# datalogger.net
KiCad netlist of a schematic drawn in Altium Designer
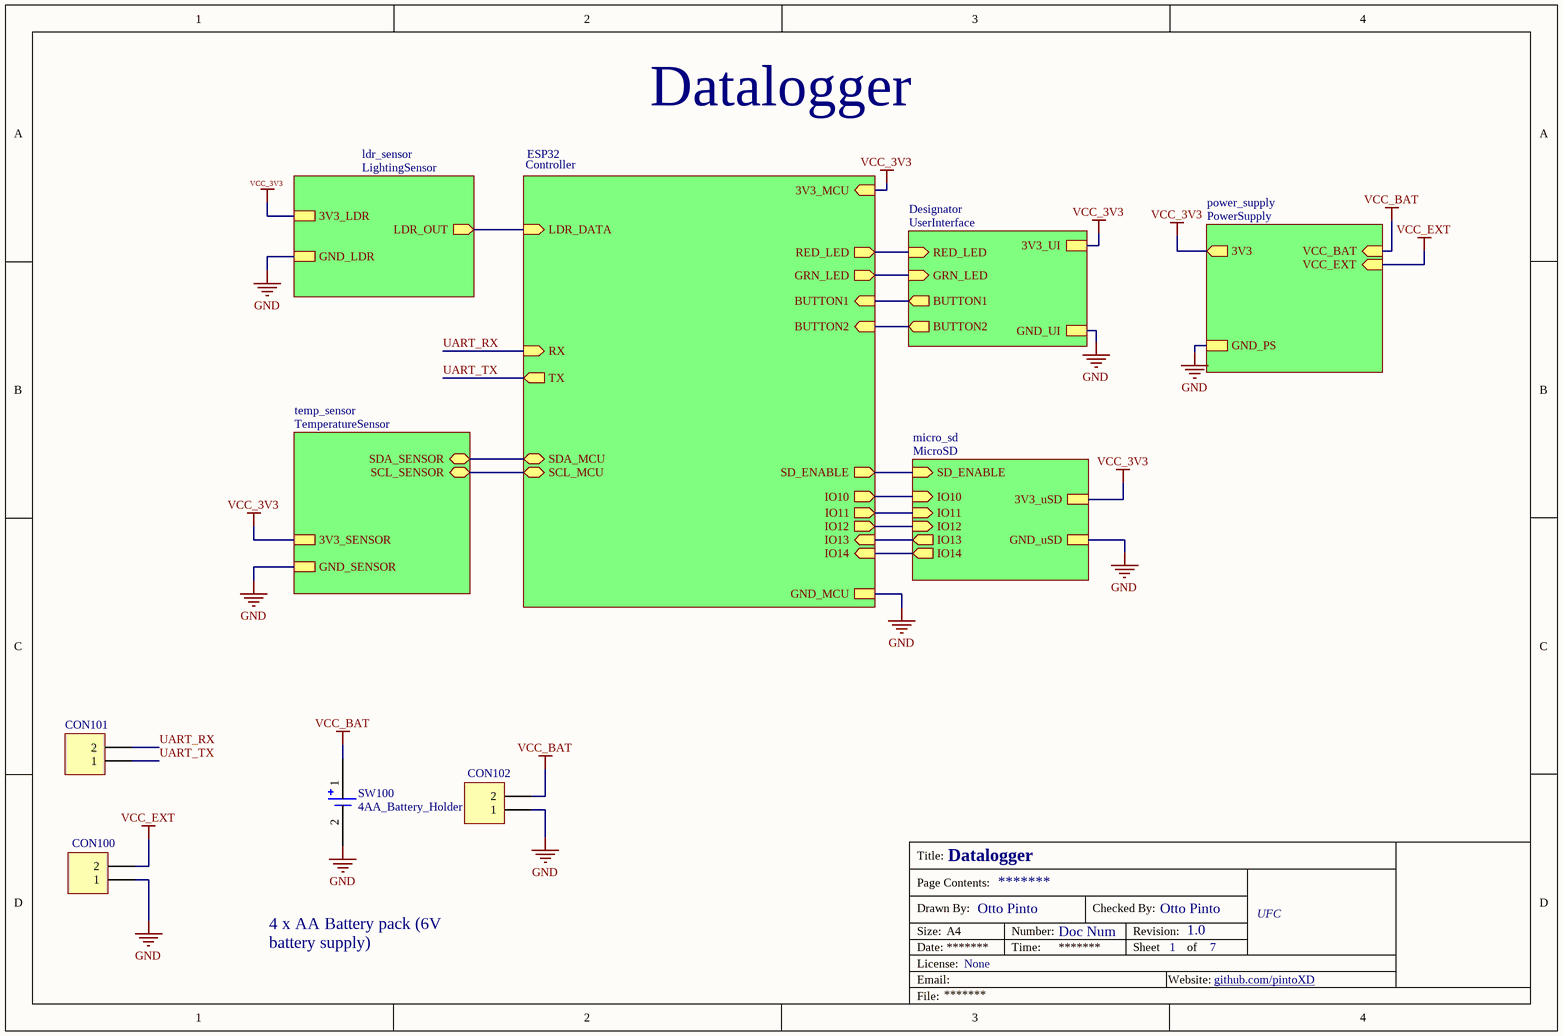
[diagram p0: datalogger.SchDoc]

(export (version "E")
  (design (tool "Eeschema 10.0.6"))
  (components
    (comp (ref "CON100")
      (value "PIN HEADER 2POS")
      (footprint "FP-TSW-102-07-G-S-MFG")
      (description "Conn Unshrouded Header HDR 2 POS 2.54mm Solder ST Top Entry Thru-Hole Bulk")
      (fields (field (name "MANUFACTURER PART NUMBER") "TSW-102-07-G-S"))
      (libsource (lib "Mobit Brasil Ltda") (part "Pin Header 2POS"))
    )
    (comp (ref "CON101")
      (value "PIN HEADER 2POS")
      (footprint "FP-TSW-102-07-G-S-MFG")
      (description "Conn Unshrouded Header HDR 2 POS 2.54mm Solder ST Top Entry Thru-Hole Bulk")
      (fields (field (name "MANUFACTURER PART NUMBER") "TSW-102-07-G-S"))
      (libsource (lib "Mobit Brasil Ltda") (part "Pin Header 2POS"))
    )
    (comp (ref "CON102")
      (value "PIN HEADER 2POS")
      (footprint "FP-TSW-102-07-G-S-MFG")
      (description "Conn Unshrouded Header HDR 2 POS 2.54mm Solder ST Top Entry Thru-Hole Bulk")
      (fields (field (name "MANUFACTURER PART NUMBER") "TSW-102-07-G-S"))
      (libsource (lib "Mobit Brasil Ltda") (part "Pin Header 2POS"))
    )
    (comp (ref "SW100")
      (value "4AA_Battery_Holder")
      (footprint "4AAA_BATTERY_HOLDER")
      (fields
        (field (name "MANUFACTURER") "Bud Industries")
        (field (name "MANUFACTURER PART NUMBER") "HH-3633")
      )
      (libsource (lib "lib_datalogger") (part "4AAA_battery_holder"))
    )
  )
  (nets
    (net (code "14") (name "/UART_RX") (class "Default")
      (node (ref "CON101") (pin "2") (pinfunction "2_2") (pintype "passive"))
    )
    (net (code "15") (name "/UART_TX") (class "Default")
      (node (ref "CON101") (pin "1") (pinfunction "1_1") (pintype "passive"))
    )
    (net (code "16") (name "GND") (class "Default")
      (node (ref "CON100") (pin "1") (pinfunction "1_1") (pintype "passive"))
      (node (ref "CON102") (pin "1") (pinfunction "1_1") (pintype "passive"))
      (node (ref "SW100") (pin "2") (pinfunction "2_2") (pintype "passive"))
    )
    (net (code "18") (name "VCC_BAT") (class "Default")
      (node (ref "CON102") (pin "2") (pinfunction "2_2") (pintype "passive"))
      (node (ref "SW100") (pin "1") (pinfunction "1_1") (pintype "passive"))
    )
    (net (code "19") (name "VCC_EXT") (class "Default")
      (node (ref "CON100") (pin "2") (pinfunction "2_2") (pintype "passive"))
    )
  )
)
